# PCB_GW_ESP32_DIO_RS485.net
KiCad netlist of a schematic drawn in EAGLE
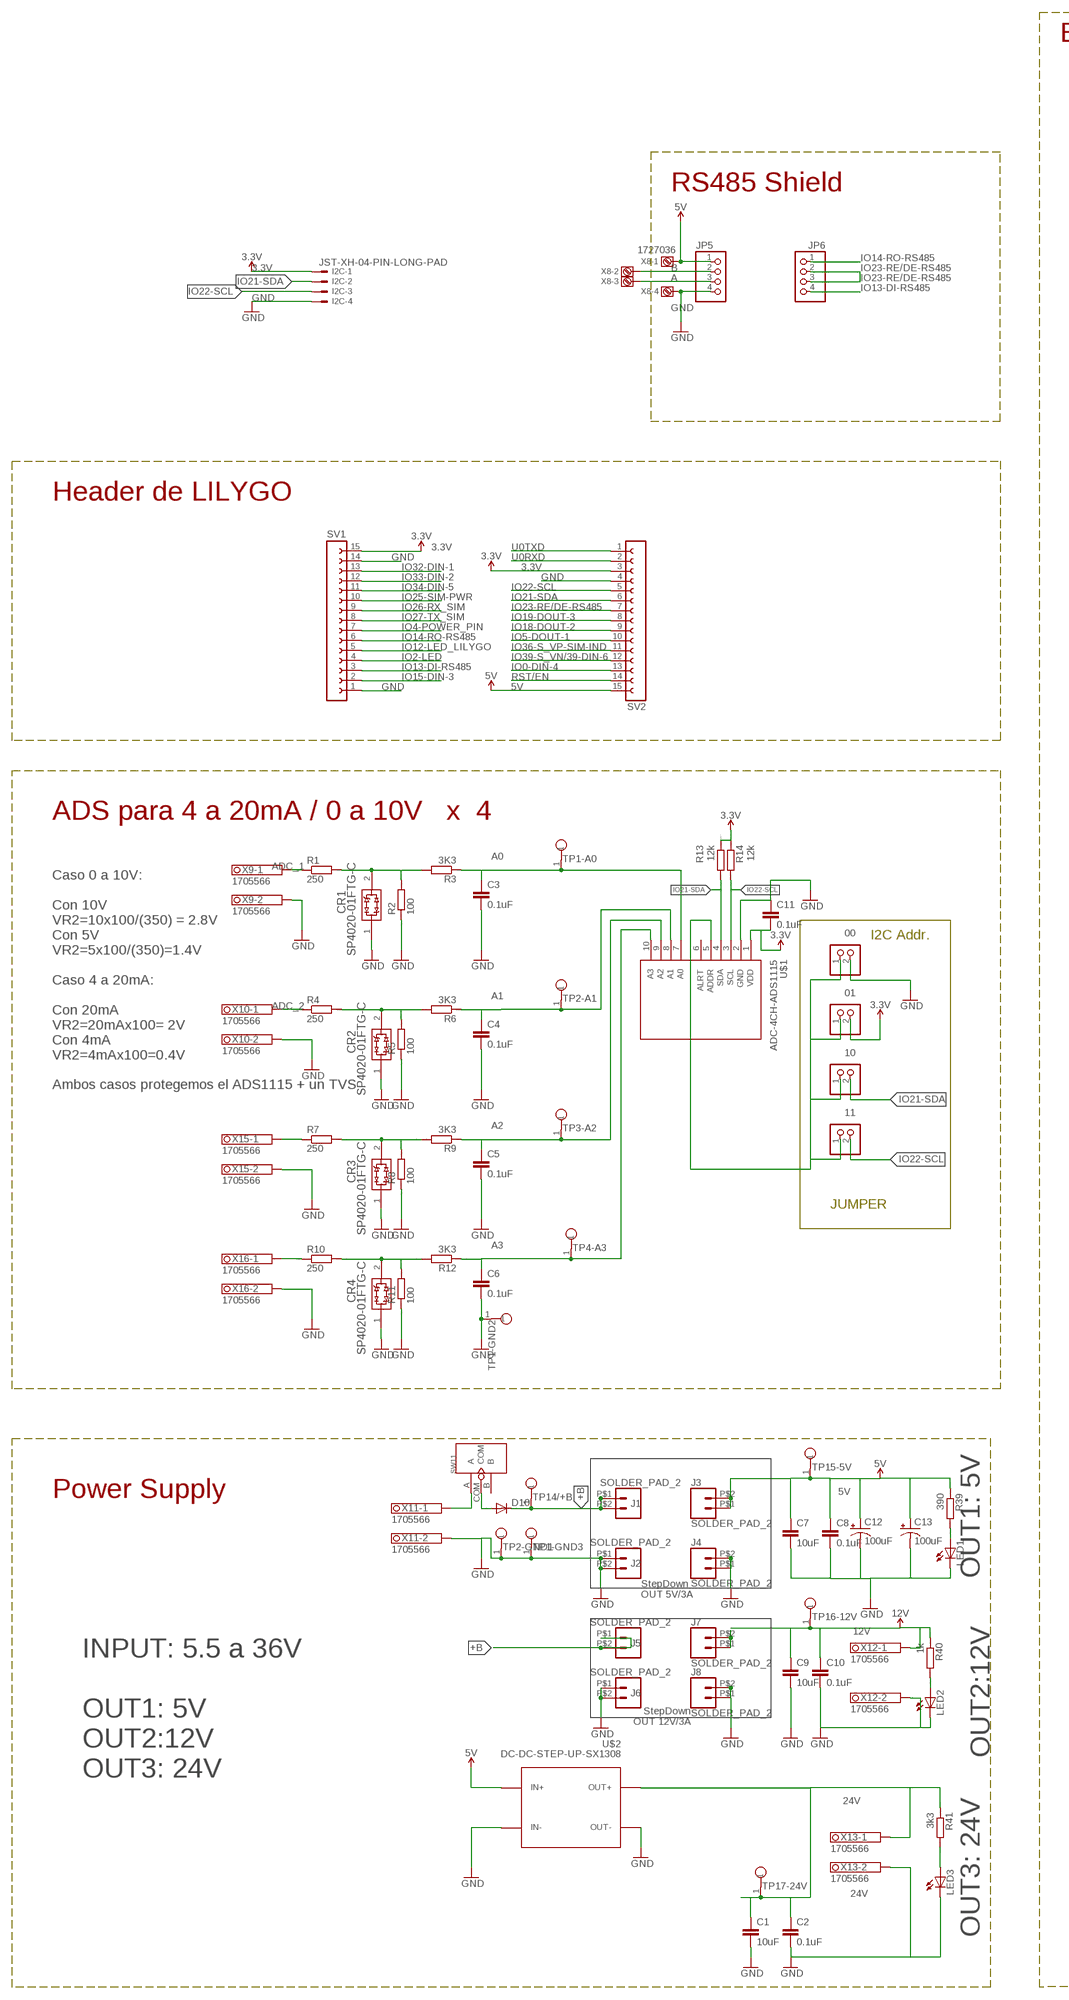
[diagram p0: schematic, sheet 1, part 1 of 2]
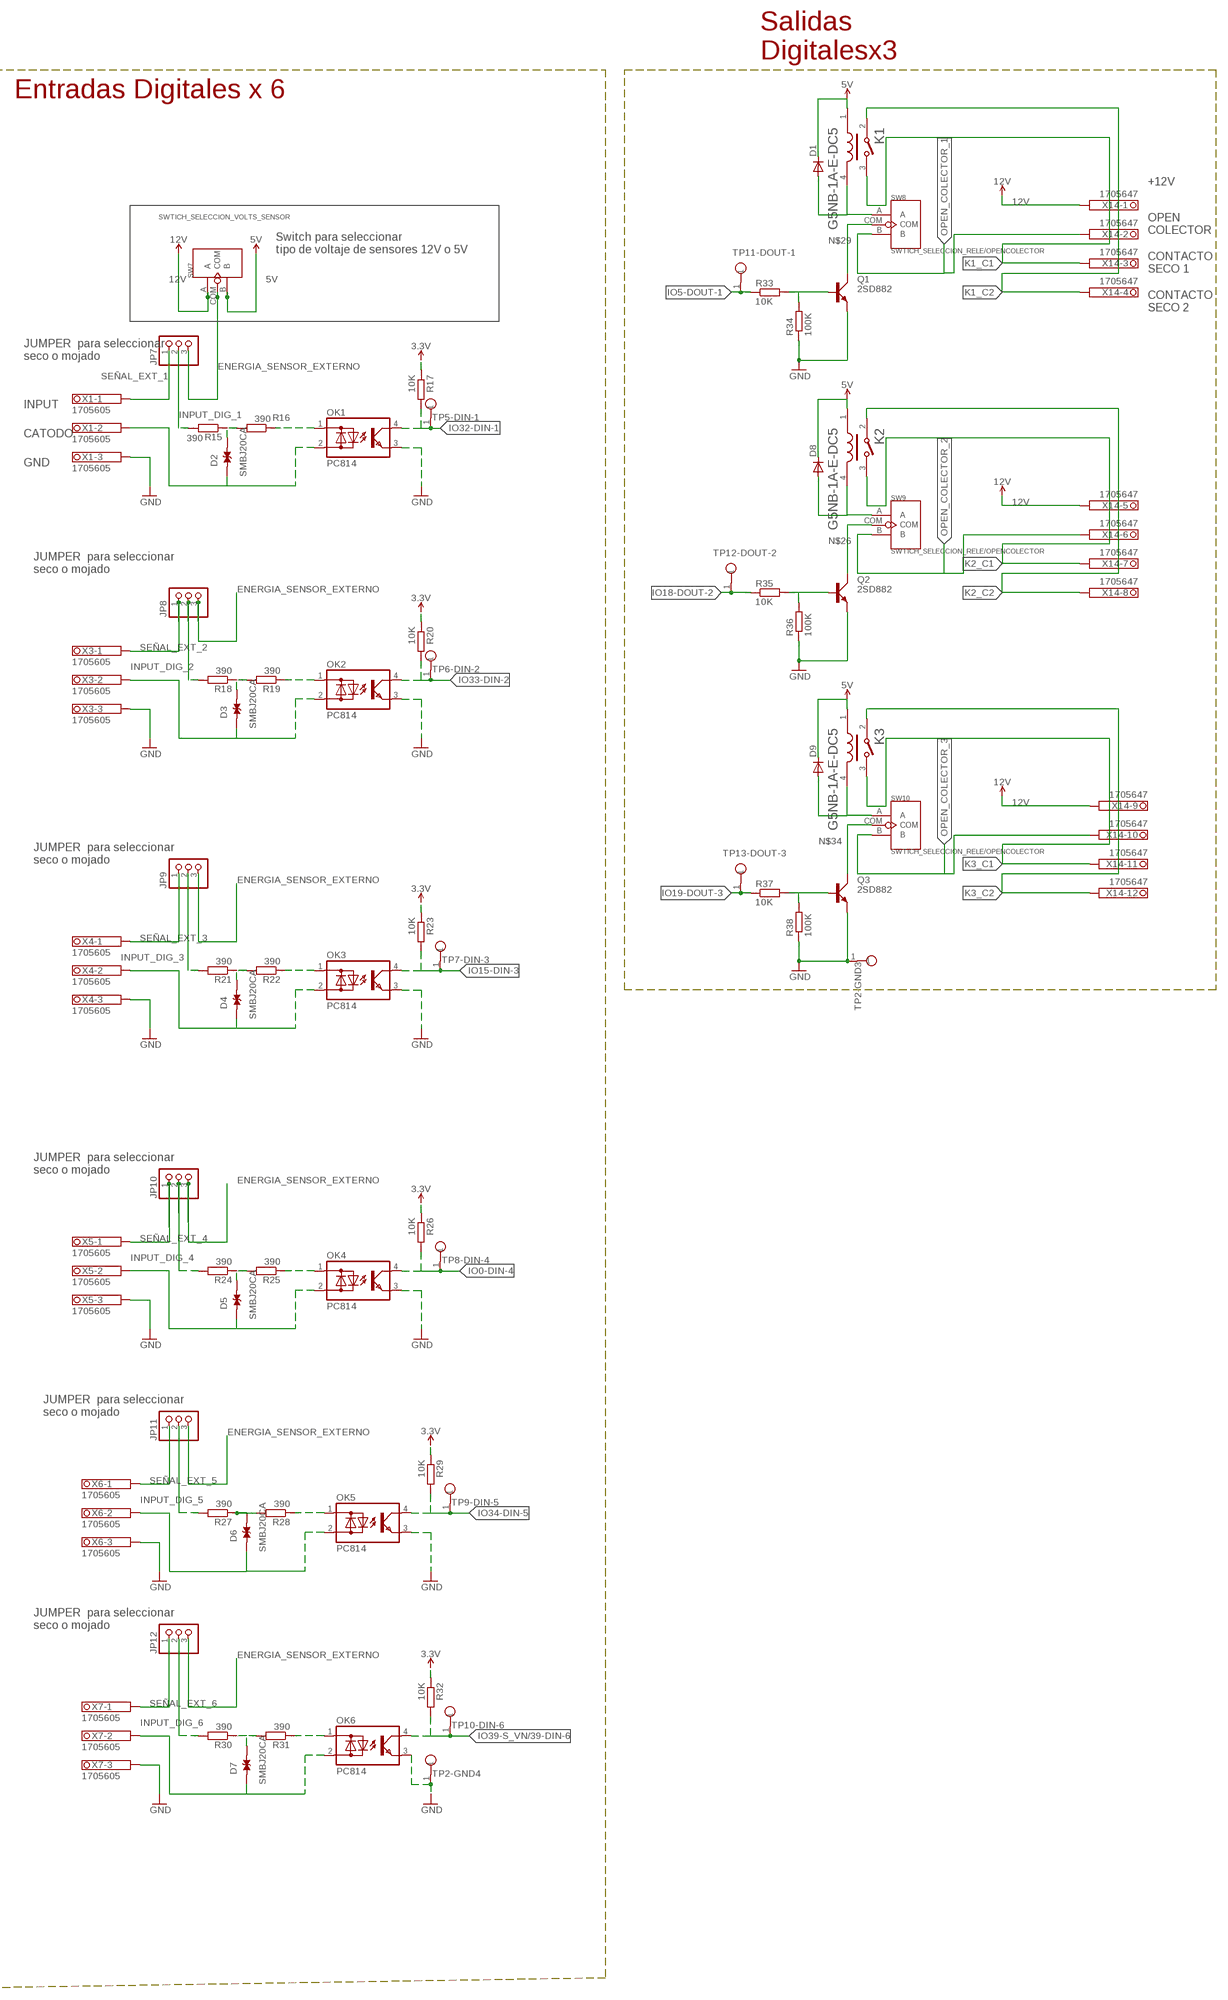
[diagram p1: schematic, sheet 1, part 2 of 2]

(export (version "E")
  (design (tool "Eeschema 10.0.6"))
  (components
    (comp (ref "C1")
      (value "10uF")
      (footprint "eagle-import:1206")
      (libsource (lib "eagle-import") (part "10UF-1206-6.3V-20%"))
    )
    (comp (ref "C2")
      (value "0.1uF")
      (footprint "eagle-import:1206")
      (libsource (lib "eagle-import") (part "1.0UF-1206-50V-10%"))
    )
    (comp (ref "C3")
      (value "0.1uF")
      (footprint "eagle-import:1206")
      (libsource (lib "eagle-import") (part "1.0UF-1206-50V-10%"))
    )
    (comp (ref "C4")
      (value "0.1uF")
      (footprint "eagle-import:1206")
      (libsource (lib "eagle-import") (part "1.0UF-1206-50V-10%"))
    )
    (comp (ref "C5")
      (value "0.1uF")
      (footprint "eagle-import:1206")
      (libsource (lib "eagle-import") (part "1.0UF-1206-50V-10%"))
    )
    (comp (ref "C6")
      (value "0.1uF")
      (footprint "eagle-import:1206")
      (libsource (lib "eagle-import") (part "1.0UF-1206-50V-10%"))
    )
    (comp (ref "C7")
      (value "10uF")
      (footprint "eagle-import:1206")
      (libsource (lib "eagle-import") (part "10UF-1206-6.3V-20%"))
    )
    (comp (ref "C8")
      (value "0.1uF")
      (footprint "eagle-import:1206")
      (libsource (lib "eagle-import") (part "1.0UF-1206-50V-10%"))
    )
    (comp (ref "C9")
      (value "10uF")
      (footprint "eagle-import:1206")
      (libsource (lib "eagle-import") (part "10UF-1206-6.3V-20%"))
    )
    (comp (ref "C10")
      (value "0.1uF")
      (footprint "eagle-import:1206")
      (libsource (lib "eagle-import") (part "1.0UF-1206-50V-10%"))
    )
    (comp (ref "C11")
      (value "0.1uF")
      (footprint "eagle-import:1206")
      (libsource (lib "eagle-import") (part "1.0UF-1206-50V-10%"))
    )
    (comp (ref "C12")
      (value "100uF")
      (footprint "eagle-import:CPOL-RADIAL-2.5MM-6.5MM")
      (libsource (lib "eagle-import") (part "100UF-POLAR-RADIAL-2.5MM-25V-20%"))
    )
    (comp (ref "C13")
      (value "100uF")
      (footprint "eagle-import:PANASONIC_D")
      (libsource (lib "eagle-import") (part "100UF-POLAR-25V-20%-SMD(ELEC)"))
    )
    (comp (ref "CR1")
      (value "SP4020-01FTG-C")
      (footprint "eagle-import:SOD323_LTF")
      (fields (field (name "COPYRIGHT") "Copyright (C) 2023 Ultra Librarian. All rights reserved."))
      (libsource (lib "eagle-import") (part "SP4020-01FTG-C"))
    )
    (comp (ref "CR2")
      (value "SP4020-01FTG-C")
      (footprint "eagle-import:SOD323_LTF")
      (fields (field (name "COPYRIGHT") "Copyright (C) 2023 Ultra Librarian. All rights reserved."))
      (libsource (lib "eagle-import") (part "SP4020-01FTG-C"))
    )
    (comp (ref "CR3")
      (value "SP4020-01FTG-C")
      (footprint "eagle-import:SOD323_LTF")
      (fields (field (name "COPYRIGHT") "Copyright (C) 2023 Ultra Librarian. All rights reserved."))
      (libsource (lib "eagle-import") (part "SP4020-01FTG-C"))
    )
    (comp (ref "CR4")
      (value "SP4020-01FTG-C")
      (footprint "eagle-import:SOD323_LTF")
      (fields (field (name "COPYRIGHT") "Copyright (C) 2023 Ultra Librarian. All rights reserved."))
      (libsource (lib "eagle-import") (part "SP4020-01FTG-C"))
    )
    (comp (ref "D1")
      (value "DIODE-DO214AC")
      (footprint "eagle-import:DO214AC")
      (libsource (lib "eagle-import") (part "DIODE-DO214AC"))
    )
    (comp (ref "D2")
      (value "SMBJ20CA")
      (footprint "eagle-import:DIOM4336X265N")
      (fields (field (name "MF") "Taiwan Semiconductor"))
      (libsource (lib "eagle-import") (part "SMBJ20CA"))
    )
    (comp (ref "D3")
      (value "SMBJ20CA")
      (footprint "eagle-import:DIOM4336X265N")
      (fields (field (name "MF") "Taiwan Semiconductor"))
      (libsource (lib "eagle-import") (part "SMBJ20CA"))
    )
    (comp (ref "D4")
      (value "SMBJ20CA")
      (footprint "eagle-import:DIOM4336X265N")
      (fields (field (name "MF") "Taiwan Semiconductor"))
      (libsource (lib "eagle-import") (part "SMBJ20CA"))
    )
    (comp (ref "D5")
      (value "SMBJ20CA")
      (footprint "eagle-import:DIOM4336X265N")
      (fields (field (name "MF") "Taiwan Semiconductor"))
      (libsource (lib "eagle-import") (part "SMBJ20CA"))
    )
    (comp (ref "D6")
      (value "SMBJ20CA")
      (footprint "eagle-import:DIOM4336X265N")
      (fields (field (name "MF") "Taiwan Semiconductor"))
      (libsource (lib "eagle-import") (part "SMBJ20CA"))
    )
    (comp (ref "D7")
      (value "SMBJ20CA")
      (footprint "eagle-import:DIOM4336X265N")
      (fields (field (name "MF") "Taiwan Semiconductor"))
      (libsource (lib "eagle-import") (part "SMBJ20CA"))
    )
    (comp (ref "D8")
      (value "DIODE-DO214AC")
      (footprint "eagle-import:DO214AC")
      (libsource (lib "eagle-import") (part "DIODE-DO214AC"))
    )
    (comp (ref "D9")
      (value "DIODE-DO214AC")
      (footprint "eagle-import:DO214AC")
      (libsource (lib "eagle-import") (part "DIODE-DO214AC"))
    )
    (comp (ref "D10")
      (value "DIODE-DO214AC")
      (footprint "eagle-import:DO214AC")
      (libsource (lib "eagle-import") (part "DIODE-DO214AC"))
    )
    (comp (ref "I2C")
      (value "JST-XH-04-PIN-LONG-PAD")
      (footprint "eagle-import:JST-XH-04-PACKAGE-LONG-PAD")
      (libsource (lib "eagle-import") (part "JST-XH-04-PIN-LONG-PAD"))
    )
    (comp (ref "J1")
      (value "SOLDER_PAD_2")
      (footprint "eagle-import:SOLDER_PAD_2")
      (libsource (lib "eagle-import") (part "SOLDER_PAD_2"))
    )
    (comp (ref "J2")
      (value "SOLDER_PAD_2")
      (footprint "eagle-import:SOLDER_PAD_2")
      (libsource (lib "eagle-import") (part "SOLDER_PAD_2"))
    )
    (comp (ref "J3")
      (value "SOLDER_PAD_2")
      (footprint "eagle-import:SOLDER_PAD_2")
      (libsource (lib "eagle-import") (part "SOLDER_PAD_2"))
    )
    (comp (ref "J4")
      (value "SOLDER_PAD_2")
      (footprint "eagle-import:SOLDER_PAD_2")
      (libsource (lib "eagle-import") (part "SOLDER_PAD_2"))
    )
    (comp (ref "J5")
      (value "SOLDER_PAD_2")
      (footprint "eagle-import:SOLDER_PAD_2")
      (libsource (lib "eagle-import") (part "SOLDER_PAD_2"))
    )
    (comp (ref "J6")
      (value "SOLDER_PAD_2")
      (footprint "eagle-import:SOLDER_PAD_2")
      (libsource (lib "eagle-import") (part "SOLDER_PAD_2"))
    )
    (comp (ref "J7")
      (value "SOLDER_PAD_2")
      (footprint "eagle-import:SOLDER_PAD_2")
      (libsource (lib "eagle-import") (part "SOLDER_PAD_2"))
    )
    (comp (ref "J8")
      (value "SOLDER_PAD_2")
      (footprint "eagle-import:SOLDER_PAD_2")
      (libsource (lib "eagle-import") (part "SOLDER_PAD_2"))
    )
    (comp (ref "JP1")
      (value "00")
      (footprint "eagle-import:1X02")
      (libsource (lib "eagle-import") (part "PINHD-1X2"))
    )
    (comp (ref "JP2")
      (value "01")
      (footprint "eagle-import:1X02")
      (libsource (lib "eagle-import") (part "PINHD-1X2"))
    )
    (comp (ref "JP3")
      (value "10")
      (footprint "eagle-import:1X02")
      (libsource (lib "eagle-import") (part "PINHD-1X2"))
    )
    (comp (ref "JP4")
      (value "11")
      (footprint "eagle-import:1X02")
      (libsource (lib "eagle-import") (part "PINHD-1X2"))
    )
    (comp (ref "JP5")
      (value "PINHD-1X4")
      (footprint "eagle-import:1X04")
      (libsource (lib "eagle-import") (part "PINHD-1X4"))
    )
    (comp (ref "JP6")
      (value "PINHD-1X4")
      (footprint "eagle-import:1X04")
      (libsource (lib "eagle-import") (part "PINHD-1X4"))
    )
    (comp (ref "JP7")
      (value "PINHD-1X3")
      (footprint "eagle-import:1X03")
      (libsource (lib "eagle-import") (part "PINHD-1X3"))
    )
    (comp (ref "JP8")
      (value "PINHD-1X3")
      (footprint "eagle-import:1X03")
      (libsource (lib "eagle-import") (part "PINHD-1X3"))
    )
    (comp (ref "JP9")
      (value "PINHD-1X3")
      (footprint "eagle-import:1X03")
      (libsource (lib "eagle-import") (part "PINHD-1X3"))
    )
    (comp (ref "JP10")
      (value "PINHD-1X3")
      (footprint "eagle-import:1X03")
      (libsource (lib "eagle-import") (part "PINHD-1X3"))
    )
    (comp (ref "JP11")
      (value "PINHD-1X3")
      (footprint "eagle-import:1X03")
      (libsource (lib "eagle-import") (part "PINHD-1X3"))
    )
    (comp (ref "JP12")
      (value "PINHD-1X3")
      (footprint "eagle-import:1X03")
      (libsource (lib "eagle-import") (part "PINHD-1X3"))
    )
    (comp (ref "K1")
      (value "OMRON_G5NB-1A-E-DC5OMRON_G5NB-1A-E-DC5_0_0")
      (footprint "eagle-import:OMRON_G5NB-1A-E-DC5_0")
      (fields
        (field (name "DIGIKEY_PART_NUMBER") "Z2771-ND")
        (field (name "MF") "Omron")
        (field (name "MOUSER_PART_NUMBER") "653-G5NB-1A-E-DC5")
      )
      (libsource (lib "eagle-import") (part "OMRON_G5NB-1A-E-DC5OMRON_G5NB-1A-E-DC5_0_0"))
    )
    (comp (ref "K2")
      (value "OMRON_G5NB-1A-E-DC5OMRON_G5NB-1A-E-DC5_0_0")
      (footprint "eagle-import:OMRON_G5NB-1A-E-DC5_0")
      (fields
        (field (name "DIGIKEY_PART_NUMBER") "Z2771-ND")
        (field (name "MF") "Omron")
        (field (name "MOUSER_PART_NUMBER") "653-G5NB-1A-E-DC5")
      )
      (libsource (lib "eagle-import") (part "OMRON_G5NB-1A-E-DC5OMRON_G5NB-1A-E-DC5_0_0"))
    )
    (comp (ref "K3")
      (value "OMRON_G5NB-1A-E-DC5OMRON_G5NB-1A-E-DC5_0_0")
      (footprint "eagle-import:OMRON_G5NB-1A-E-DC5_0")
      (fields
        (field (name "DIGIKEY_PART_NUMBER") "Z2771-ND")
        (field (name "MF") "Omron")
        (field (name "MOUSER_PART_NUMBER") "653-G5NB-1A-E-DC5")
      )
      (libsource (lib "eagle-import") (part "OMRON_G5NB-1A-E-DC5OMRON_G5NB-1A-E-DC5_0_0"))
    )
    (comp (ref "LED1")
      (value "LEDCHIPLED_1206")
      (footprint "eagle-import:CHIPLED_1206")
      (libsource (lib "eagle-import") (part "LEDCHIPLED_1206"))
    )
    (comp (ref "LED2")
      (value "LEDCHIPLED_1206")
      (footprint "eagle-import:CHIPLED_1206")
      (libsource (lib "eagle-import") (part "LEDCHIPLED_1206"))
    )
    (comp (ref "LED3")
      (value "LEDCHIPLED_1206")
      (footprint "eagle-import:CHIPLED_1206")
      (libsource (lib "eagle-import") (part "LEDCHIPLED_1206"))
    )
    (comp (ref "OK1")
      (value "PC814")
      (footprint "eagle-import:DIL04")
      (libsource (lib "eagle-import") (part "PC814"))
    )
    (comp (ref "OK2")
      (value "PC814")
      (footprint "eagle-import:DIL04")
      (libsource (lib "eagle-import") (part "PC814"))
    )
    (comp (ref "OK3")
      (value "PC814")
      (footprint "eagle-import:DIL04")
      (libsource (lib "eagle-import") (part "PC814"))
    )
    (comp (ref "OK4")
      (value "PC814")
      (footprint "eagle-import:DIL04")
      (libsource (lib "eagle-import") (part "PC814"))
    )
    (comp (ref "OK5")
      (value "PC814")
      (footprint "eagle-import:DIL04")
      (libsource (lib "eagle-import") (part "PC814"))
    )
    (comp (ref "OK6")
      (value "PC814")
      (footprint "eagle-import:DIL04")
      (libsource (lib "eagle-import") (part "PC814"))
    )
    (comp (ref "Q1")
      (value "2SD882")
      (footprint "eagle-import:TO126AV")
      (libsource (lib "eagle-import") (part "BD437"))
    )
    (comp (ref "Q2")
      (value "2SD882")
      (footprint "eagle-import:TO126AV")
      (libsource (lib "eagle-import") (part "BD437"))
    )
    (comp (ref "Q3")
      (value "2SD882")
      (footprint "eagle-import:TO126AV")
      (libsource (lib "eagle-import") (part "BD437"))
    )
    (comp (ref "R1")
      (value "250")
      (footprint "eagle-import:R1206")
      (libsource (lib "eagle-import") (part "RR1206"))
    )
    (comp (ref "R2")
      (value "100")
      (footprint "eagle-import:R1206")
      (libsource (lib "eagle-import") (part "RR1206"))
    )
    (comp (ref "R3")
      (value "3K3")
      (footprint "eagle-import:R1206")
      (libsource (lib "eagle-import") (part "RR1206"))
    )
    (comp (ref "R4")
      (value "250")
      (footprint "eagle-import:R1206")
      (libsource (lib "eagle-import") (part "RR1206"))
    )
    (comp (ref "R5")
      (value "100")
      (footprint "eagle-import:R1206")
      (libsource (lib "eagle-import") (part "RR1206"))
    )
    (comp (ref "R6")
      (value "3K3")
      (footprint "eagle-import:R1206")
      (libsource (lib "eagle-import") (part "RR1206"))
    )
    (comp (ref "R7")
      (value "250")
      (footprint "eagle-import:R1206")
      (libsource (lib "eagle-import") (part "RR1206"))
    )
    (comp (ref "R8")
      (value "100")
      (footprint "eagle-import:R1206")
      (libsource (lib "eagle-import") (part "RR1206"))
    )
    (comp (ref "R9")
      (value "3K3")
      (footprint "eagle-import:R1206")
      (libsource (lib "eagle-import") (part "RR1206"))
    )
    (comp (ref "R10")
      (value "250")
      (footprint "eagle-import:R1206")
      (libsource (lib "eagle-import") (part "RR1206"))
    )
    (comp (ref "R11")
      (value "100")
      (footprint "eagle-import:R1206")
      (libsource (lib "eagle-import") (part "RR1206"))
    )
    (comp (ref "R12")
      (value "3K3")
      (footprint "eagle-import:R1206")
      (libsource (lib "eagle-import") (part "RR1206"))
    )
    (comp (ref "R13")
      (value "12k")
      (footprint "eagle-import:R1206")
      (libsource (lib "eagle-import") (part "RR1206"))
    )
    (comp (ref "R14")
      (value "12k")
      (footprint "eagle-import:R1206")
      (libsource (lib "eagle-import") (part "RR1206"))
    )
    (comp (ref "R15")
      (value "390")
      (footprint "eagle-import:R1206")
      (libsource (lib "eagle-import") (part "RR1206"))
    )
    (comp (ref "R16")
      (value "390")
      (footprint "eagle-import:R1206")
      (libsource (lib "eagle-import") (part "RR1206"))
    )
    (comp (ref "R17")
      (value "10K")
      (footprint "eagle-import:R1206")
      (libsource (lib "eagle-import") (part "RR1206"))
    )
    (comp (ref "R18")
      (value "390")
      (footprint "eagle-import:R1206")
      (libsource (lib "eagle-import") (part "RR1206"))
    )
    (comp (ref "R19")
      (value "390")
      (footprint "eagle-import:R1206")
      (libsource (lib "eagle-import") (part "RR1206"))
    )
    (comp (ref "R20")
      (value "10K")
      (footprint "eagle-import:R1206")
      (libsource (lib "eagle-import") (part "RR1206"))
    )
    (comp (ref "R21")
      (value "390")
      (footprint "eagle-import:R1206")
      (libsource (lib "eagle-import") (part "RR1206"))
    )
    (comp (ref "R22")
      (value "390")
      (footprint "eagle-import:R1206")
      (libsource (lib "eagle-import") (part "RR1206"))
    )
    (comp (ref "R23")
      (value "10K")
      (footprint "eagle-import:R1206")
      (libsource (lib "eagle-import") (part "RR1206"))
    )
    (comp (ref "R24")
      (value "390")
      (footprint "eagle-import:R1206")
      (libsource (lib "eagle-import") (part "RR1206"))
    )
    (comp (ref "R25")
      (value "390")
      (footprint "eagle-import:R1206")
      (libsource (lib "eagle-import") (part "RR1206"))
    )
    (comp (ref "R26")
      (value "10K")
      (footprint "eagle-import:R1206")
      (libsource (lib "eagle-import") (part "RR1206"))
    )
    (comp (ref "R27")
      (value "390")
      (footprint "eagle-import:R1206")
      (libsource (lib "eagle-import") (part "RR1206"))
    )
    (comp (ref "R28")
      (value "390")
      (footprint "eagle-import:R1206")
      (libsource (lib "eagle-import") (part "RR1206"))
    )
    (comp (ref "R29")
      (value "10K")
      (footprint "eagle-import:R1206")
      (libsource (lib "eagle-import") (part "RR1206"))
    )
    (comp (ref "R30")
      (value "390")
      (footprint "eagle-import:R1206")
      (libsource (lib "eagle-import") (part "RR1206"))
    )
    (comp (ref "R31")
      (value "390")
      (footprint "eagle-import:R1206")
      (libsource (lib "eagle-import") (part "RR1206"))
    )
    (comp (ref "R32")
      (value "10K")
      (footprint "eagle-import:R1206")
      (libsource (lib "eagle-import") (part "RR1206"))
    )
    (comp (ref "R33")
      (value "10K")
      (footprint "eagle-import:R1206")
      (libsource (lib "eagle-import") (part "RR1206"))
    )
    (comp (ref "R34")
      (value "100K")
      (footprint "eagle-import:R1206")
      (libsource (lib "eagle-import") (part "RR1206"))
    )
    (comp (ref "R35")
      (value "10K")
      (footprint "eagle-import:R1206")
      (libsource (lib "eagle-import") (part "RR1206"))
    )
    (comp (ref "R36")
      (value "100K")
      (footprint "eagle-import:R1206")
      (libsource (lib "eagle-import") (part "RR1206"))
    )
    (comp (ref "R37")
      (value "10K")
      (footprint "eagle-import:R1206")
      (libsource (lib "eagle-import") (part "RR1206"))
    )
    (comp (ref "R38")
      (value "100K")
      (footprint "eagle-import:R1206")
      (libsource (lib "eagle-import") (part "RR1206"))
    )
    (comp (ref "R39")
      (value "390")
      (footprint "eagle-import:R1206")
      (libsource (lib "eagle-import") (part "RR1206"))
    )
    (comp (ref "R40")
      (value "1k")
      (footprint "eagle-import:R1206")
      (libsource (lib "eagle-import") (part "RR1206"))
    )
    (comp (ref "R41")
      (value "3k3")
      (footprint "eagle-import:R1206")
      (libsource (lib "eagle-import") (part "RR1206"))
    )
    (comp (ref "SV1")
      (value "FE15-1")
      (footprint "eagle-import:FE15")
      (libsource (lib "eagle-import") (part "FE15-1"))
    )
    (comp (ref "SV2")
      (value "FE15-1")
      (footprint "eagle-import:FE15")
      (libsource (lib "eagle-import") (part "FE15-1"))
    )
    (comp (ref "SW7")
      (value "SWTICH_SELECCION_VOLTS_SENSOR")
      (footprint "eagle-import:SW5-2.0-8.8X4.4X4.7MM-90D")
      (fields (field (name "MPN") "3P-2.0-90D3P-2.0-90D-REINFORCE"))
      (libsource (lib "eagle-import") (part "DIP-TOGGLE-SWITCH-ON-ON(3+2P-8.8X4.6MM)-90D"))
    )
    (comp (ref "SW8")
      (value "SWTICH_SELECCION_RELE/OPENCOLECTOR")
      (footprint "eagle-import:SW5-2.0-8.8X4.4X4.7MM-90D")
      (fields (field (name "MPN") "3P-2.0-90D3P-2.0-90D-REINFORCE"))
      (libsource (lib "eagle-import") (part "DIP-TOGGLE-SWITCH-ON-ON(3+2P-8.8X4.6MM)-90D"))
    )
    (comp (ref "SW9")
      (value "SWTICH_SELECCION_RELE/OPENCOLECTOR")
      (footprint "eagle-import:SW5-2.0-8.8X4.4X4.7MM-90D")
      (fields (field (name "MPN") "3P-2.0-90D3P-2.0-90D-REINFORCE"))
      (libsource (lib "eagle-import") (part "DIP-TOGGLE-SWITCH-ON-ON(3+2P-8.8X4.6MM)-90D"))
    )
    (comp (ref "SW10")
      (value "SWTICH_SELECCION_RELE/OPENCOLECTOR")
      (footprint "eagle-import:SW5-2.0-8.8X4.4X4.7MM-90D")
      (fields (field (name "MPN") "3P-2.0-90D3P-2.0-90D-REINFORCE"))
      (libsource (lib "eagle-import") (part "DIP-TOGGLE-SWITCH-ON-ON(3+2P-8.8X4.6MM)-90D"))
    )
    (comp (ref "SW11")
      (value "DIP-TOGGLE-SWITCH-ON-ON(3+2P-8.8X4.6MM)-90D")
      (footprint "eagle-import:SW5-2.0-8.8X4.4X4.7MM-90D")
      (fields (field (name "MPN") "3P-2.0-90D3P-2.0-90D-REINFORCE"))
      (libsource (lib "eagle-import") (part "DIP-TOGGLE-SWITCH-ON-ON(3+2P-8.8X4.6MM)-90D"))
    )
    (comp (ref "TP1-A0")
      (value "TESTPOINT")
      (footprint "eagle-import:TESTPOINT")
      (libsource (lib "eagle-import") (part "TESTPOINT"))
    )
    (comp (ref "TP1-GND2")
      (value "TESTPOINT")
      (footprint "eagle-import:TESTPOINT")
      (libsource (lib "eagle-import") (part "TESTPOINT"))
    )
    (comp (ref "TP1-GND3")
      (value "TESTPOINT")
      (footprint "eagle-import:TESTPOINT")
      (libsource (lib "eagle-import") (part "TESTPOINT"))
    )
    (comp (ref "TP2-A1")
      (value "TESTPOINT")
      (footprint "eagle-import:TESTPOINT")
      (libsource (lib "eagle-import") (part "TESTPOINT"))
    )
    (comp (ref "TP2-GND1")
      (value "TESTPOINT")
      (footprint "eagle-import:TESTPOINT")
      (libsource (lib "eagle-import") (part "TESTPOINT"))
    )
    (comp (ref "TP2-GND3")
      (value "TESTPOINT")
      (footprint "eagle-import:TESTPOINT")
      (libsource (lib "eagle-import") (part "TESTPOINT"))
    )
    (comp (ref "TP2-GND4")
      (value "TESTPOINT")
      (footprint "eagle-import:TESTPOINT")
      (libsource (lib "eagle-import") (part "TESTPOINT"))
    )
    (comp (ref "TP3-A2")
      (value "TESTPOINT")
      (footprint "eagle-import:TESTPOINT")
      (libsource (lib "eagle-import") (part "TESTPOINT"))
    )
    (comp (ref "TP4-A3")
      (value "TESTPOINT")
      (footprint "eagle-import:TESTPOINT")
      (libsource (lib "eagle-import") (part "TESTPOINT"))
    )
    (comp (ref "TP5-DIN-1")
      (value "TESTPOINT")
      (footprint "eagle-import:TESTPOINT")
      (libsource (lib "eagle-import") (part "TESTPOINT"))
    )
    (comp (ref "TP6-DIN-2")
      (value "TESTPOINT")
      (footprint "eagle-import:TESTPOINT")
      (libsource (lib "eagle-import") (part "TESTPOINT"))
    )
    (comp (ref "TP7-DIN-3")
      (value "TESTPOINT")
      (footprint "eagle-import:TESTPOINT")
      (libsource (lib "eagle-import") (part "TESTPOINT"))
    )
    (comp (ref "TP8-DIN-4")
      (value "TESTPOINT")
      (footprint "eagle-import:TESTPOINT")
      (libsource (lib "eagle-import") (part "TESTPOINT"))
    )
    (comp (ref "TP9-DIN-5")
      (value "TESTPOINT")
      (footprint "eagle-import:TESTPOINT")
      (libsource (lib "eagle-import") (part "TESTPOINT"))
    )
    (comp (ref "TP10-DIN-6")
      (value "TESTPOINT")
      (footprint "eagle-import:TESTPOINT")
      (libsource (lib "eagle-import") (part "TESTPOINT"))
    )
    (comp (ref "TP11-DOUT-1")
      (value "TESTPOINT")
      (footprint "eagle-import:TESTPOINT")
      (libsource (lib "eagle-import") (part "TESTPOINT"))
    )
    (comp (ref "TP12-DOUT-2")
      (value "TESTPOINT")
      (footprint "eagle-import:TESTPOINT")
      (libsource (lib "eagle-import") (part "TESTPOINT"))
    )
    (comp (ref "TP13-DOUT-3")
      (value "TESTPOINT")
      (footprint "eagle-import:TESTPOINT")
      (libsource (lib "eagle-import") (part "TESTPOINT"))
    )
    (comp (ref "TP14/+B")
      (value "TESTPOINT")
      (footprint "eagle-import:TESTPOINT")
      (libsource (lib "eagle-import") (part "TESTPOINT"))
    )
    (comp (ref "TP15-5V")
      (value "TESTPOINT")
      (footprint "eagle-import:TESTPOINT")
      (libsource (lib "eagle-import") (part "TESTPOINT"))
    )
    (comp (ref "TP16-12V")
      (value "TESTPOINT")
      (footprint "eagle-import:TESTPOINT")
      (libsource (lib "eagle-import") (part "TESTPOINT"))
    )
    (comp (ref "TP17-24V")
      (value "TESTPOINT")
      (footprint "eagle-import:TESTPOINT")
      (libsource (lib "eagle-import") (part "TESTPOINT"))
    )
    (comp (ref "U$1")
      (value "ADC-4CH-ADS1115")
      (footprint "eagle-import:ADC-4CH-ADS1115")
      (libsource (lib "eagle-import") (part "ADC-4CH-ADS1115"))
    )
    (comp (ref "U$2")
      (value "DC-DC-STEP-UP-SX1308")
      (footprint "eagle-import:DC-DC-STEP-UP-SX1308")
      (libsource (lib "eagle-import") (part "DC-DC-STEP-UP-SX1308"))
    )
    (comp (ref "X1")
      (value "1705605")
      (footprint "eagle-import:1705605")
      (libsource (lib "eagle-import") (part "1705605"))
    )
    (comp (ref "X3")
      (value "1705605")
      (footprint "eagle-import:1705605")
      (libsource (lib "eagle-import") (part "1705605"))
    )
    (comp (ref "X4")
      (value "1705605")
      (footprint "eagle-import:1705605")
      (libsource (lib "eagle-import") (part "1705605"))
    )
    (comp (ref "X5")
      (value "1705605")
      (footprint "eagle-import:1705605")
      (libsource (lib "eagle-import") (part "1705605"))
    )
    (comp (ref "X6")
      (value "1705605")
      (footprint "eagle-import:1705605")
      (libsource (lib "eagle-import") (part "1705605"))
    )
    (comp (ref "X7")
      (value "1705605")
      (footprint "eagle-import:1705605")
      (libsource (lib "eagle-import") (part "1705605"))
    )
    (comp (ref "X8")
      (value "1727036")
      (footprint "eagle-import:1727036")
      (fields (field (name "MF") "FARNELL"))
      (libsource (lib "eagle-import") (part "1727036"))
    )
    (comp (ref "X9")
      (value "1705566")
      (footprint "eagle-import:1705566")
      (libsource (lib "eagle-import") (part "1705566"))
    )
    (comp (ref "X10")
      (value "1705566")
      (footprint "eagle-import:1705566")
      (libsource (lib "eagle-import") (part "1705566"))
    )
    (comp (ref "X11")
      (value "1705566")
      (footprint "eagle-import:1705566")
      (libsource (lib "eagle-import") (part "1705566"))
    )
    (comp (ref "X12")
      (value "1705566")
      (footprint "eagle-import:1705566")
      (libsource (lib "eagle-import") (part "1705566"))
    )
    (comp (ref "X13")
      (value "1705566")
      (footprint "eagle-import:1705566")
      (libsource (lib "eagle-import") (part "1705566"))
    )
    (comp (ref "X14")
      (value "1705647")
      (footprint "eagle-import:1705647")
      (libsource (lib "eagle-import") (part "1705647"))
    )
    (comp (ref "X15")
      (value "1705566")
      (footprint "eagle-import:1705566")
      (libsource (lib "eagle-import") (part "1705566"))
    )
    (comp (ref "X16")
      (value "1705566")
      (footprint "eagle-import:1705566")
      (libsource (lib "eagle-import") (part "1705566"))
    )
  )
  (nets
    (net (code "1") (name "+B") (class "Default")
      (node (ref "D10") (pin "C") (pinfunction "C_C") (pintype "passive"))
      (node (ref "J1") (pin "P$1") (pinfunction "1_P$1") (pintype "passive"))
      (node (ref "J1") (pin "P$2") (pinfunction "2_P$2") (pintype "passive"))
      (node (ref "J5") (pin "P$1") (pinfunction "1_P$1") (pintype "passive"))
      (node (ref "J5") (pin "P$2") (pinfunction "2_P$2") (pintype "passive"))
      (node (ref "TP14/+B") (pin "1") (pinfunction "1_1") (pintype "passive"))
    )
    (net (code "2") (name "/24V") (class "Default")
      (node (ref "C1") (pin "1") (pinfunction "1_1") (pintype "passive"))
      (node (ref "C2") (pin "1") (pinfunction "1_1") (pintype "passive"))
      (node (ref "R41") (pin "1") (pinfunction "1_1") (pintype "passive"))
      (node (ref "TP17-24V") (pin "1") (pinfunction "1_1") (pintype "passive"))
      (node (ref "U$2") (pin "OUT+") (pinfunction "OUT+_OUT+") (pintype "bidirectional"))
      (node (ref "X13") (pin "1.1") (pinfunction "1A_1.1") (pintype "passive"))
      (node (ref "X13") (pin "1.2") (pinfunction "1A_1.2") (pintype "passive"))
    )
    (net (code "3") (name "/A") (class "Default")
      (node (ref "JP5") (pin "3") (pinfunction "3_3") (pintype "passive"))
      (node (ref "X8") (pin "3") (pinfunction "1_3") (pintype "passive"))
    )
    (net (code "4") (name "/A0") (class "Default")
      (node (ref "C3") (pin "1") (pinfunction "1_1") (pintype "passive"))
      (node (ref "R3") (pin "1") (pinfunction "1_1") (pintype "passive"))
      (node (ref "TP1-A0") (pin "1") (pinfunction "1_1") (pintype "passive"))
      (node (ref "U$1") (pin "7") (pinfunction "A0_7") (pintype "input"))
    )
    (net (code "5") (name "/A1") (class "Default")
      (node (ref "C4") (pin "1") (pinfunction "1_1") (pintype "passive"))
      (node (ref "R6") (pin "1") (pinfunction "1_1") (pintype "passive"))
      (node (ref "TP2-A1") (pin "1") (pinfunction "1_1") (pintype "passive"))
      (node (ref "U$1") (pin "8") (pinfunction "A1_8") (pintype "input"))
    )
    (net (code "6") (name "/A2") (class "Default")
      (node (ref "C5") (pin "1") (pinfunction "1_1") (pintype "passive"))
      (node (ref "R9") (pin "1") (pinfunction "1_1") (pintype "passive"))
      (node (ref "TP3-A2") (pin "1") (pinfunction "1_1") (pintype "passive"))
      (node (ref "U$1") (pin "9") (pinfunction "A2_9") (pintype "input"))
    )
    (net (code "7") (name "/A3") (class "Default")
      (node (ref "C6") (pin "1") (pinfunction "1_1") (pintype "passive"))
      (node (ref "R12") (pin "1") (pinfunction "1_1") (pintype "passive"))
      (node (ref "TP4-A3") (pin "1") (pinfunction "1_1") (pintype "passive"))
      (node (ref "U$1") (pin "10") (pinfunction "A3_10") (pintype "input"))
    )
    (net (code "8") (name "/ADC_1") (class "Default")
      (node (ref "R1") (pin "1") (pinfunction "1_1") (pintype "passive"))
      (node (ref "X9") (pin "1.1") (pinfunction "1A_1.1") (pintype "passive"))
      (node (ref "X9") (pin "1.2") (pinfunction "1A_1.2") (pintype "passive"))
    )
    (net (code "9") (name "/ADC_2") (class "Default")
      (node (ref "R4") (pin "1") (pinfunction "1_1") (pintype "passive"))
      (node (ref "X10") (pin "1.1") (pinfunction "1A_1.1") (pintype "passive"))
      (node (ref "X10") (pin "1.2") (pinfunction "1A_1.2") (pintype "passive"))
    )
    (net (code "10") (name "/B") (class "Default")
      (node (ref "JP5") (pin "2") (pinfunction "2_2") (pintype "passive"))
      (node (ref "X8") (pin "2") (pinfunction "1_2") (pintype "passive"))
    )
    (net (code "11") (name "/ENERGIA_SENSOR_EXTERNO") (class "Default")
      (node (ref "JP10") (pin "3") (pinfunction "3_3") (pintype "passive"))
      (node (ref "JP11") (pin "3") (pinfunction "3_3") (pintype "passive"))
      (node (ref "JP12") (pin "3") (pinfunction "3_3") (pintype "passive"))
      (node (ref "JP7") (pin "3") (pinfunction "3_3") (pintype "passive"))
      (node (ref "JP8") (pin "3") (pinfunction "3_3") (pintype "passive"))
      (node (ref "JP9") (pin "3") (pinfunction "3_3") (pintype "passive"))
      (node (ref "SW7") (pin "COM") (pinfunction "COM_COM") (pintype "bidirectional"))
    )
    (net (code "12") (name "/INPUT_DIG_1") (class "Default")
      (node (ref "JP7") (pin "2") (pinfunction "2_2") (pintype "passive"))
      (node (ref "R15") (pin "2") (pinfunction "2_2") (pintype "passive"))
    )
    (net (code "13") (name "/INPUT_DIG_2") (class "Default")
      (node (ref "JP8") (pin "2") (pinfunction "2_2") (pintype "passive"))
      (node (ref "R18") (pin "2") (pinfunction "2_2") (pintype "passive"))
    )
    (net (code "14") (name "/INPUT_DIG_3") (class "Default")
      (node (ref "JP9") (pin "2") (pinfunction "2_2") (pintype "passive"))
      (node (ref "R21") (pin "2") (pinfunction "2_2") (pintype "passive"))
    )
    (net (code "15") (name "/INPUT_DIG_4") (class "Default")
      (node (ref "JP10") (pin "2") (pinfunction "2_2") (pintype "passive"))
      (node (ref "R24") (pin "2") (pinfunction "2_2") (pintype "passive"))
    )
    (net (code "16") (name "/INPUT_DIG_5") (class "Default")
      (node (ref "JP11") (pin "2") (pinfunction "2_2") (pintype "passive"))
      (node (ref "R27") (pin "2") (pinfunction "2_2") (pintype "passive"))
    )
    (net (code "17") (name "/INPUT_DIG_6") (class "Default")
      (node (ref "JP12") (pin "2") (pinfunction "2_2") (pintype "passive"))
      (node (ref "R30") (pin "2") (pinfunction "2_2") (pintype "passive"))
    )
    (net (code "18") (name "/IO2-LED") (class "Default")
      (node (ref "SV1") (pin "4") (pinfunction "4_4") (pintype "passive"))
    )
    (net (code "19") (name "/IO4-POWER_PIN") (class "Default")
      (node (ref "SV1") (pin "7") (pinfunction "7_7") (pintype "passive"))
    )
    (net (code "20") (name "/IO12-LED_LILYGO") (class "Default")
      (node (ref "SV1") (pin "5") (pinfunction "5_5") (pintype "passive"))
    )
    (net (code "21") (name "/IO13-DI-RS485") (class "Default")
      (node (ref "JP6") (pin "4") (pinfunction "4_4") (pintype "passive"))
      (node (ref "SV1") (pin "3") (pinfunction "3_3") (pintype "passive"))
    )
    (net (code "22") (name "/IO14-RO-RS485") (class "Default")
      (node (ref "JP6") (pin "1") (pinfunction "1_1") (pintype "passive"))
      (node (ref "SV1") (pin "6") (pinfunction "6_6") (pintype "passive"))
    )
    (net (code "23") (name "/IO23-RE{slash}DE-RS485") (class "Default")
      (node (ref "JP6") (pin "2") (pinfunction "2_2") (pintype "passive"))
      (node (ref "JP6") (pin "3") (pinfunction "3_3") (pintype "passive"))
      (node (ref "SV2") (pin "7") (pinfunction "7_7") (pintype "passive"))
    )
    (net (code "24") (name "/IO25-SIM-PWR") (class "Default")
      (node (ref "SV1") (pin "10") (pinfunction "10_10") (pintype "passive"))
    )
    (net (code "25") (name "/IO26-RX_SIM") (class "Default")
      (node (ref "SV1") (pin "9") (pinfunction "9_9") (pintype "passive"))
    )
    (net (code "26") (name "/IO27-TX_SIM") (class "Default")
      (node (ref "SV1") (pin "8") (pinfunction "8_8") (pintype "passive"))
    )
    (net (code "27") (name "/IO36-S_VP-SIM-IND") (class "Default")
      (node (ref "SV2") (pin "11") (pinfunction "11_11") (pintype "passive"))
    )
    (net (code "28") (name "/N$26") (class "Default")
      (node (ref "Q2") (pin "C") (pinfunction "C_C") (pintype "passive"))
      (node (ref "SW9") (pin "COM") (pinfunction "COM_COM") (pintype "bidirectional"))
    )
    (net (code "29") (name "/N$29") (class "Default")
      (node (ref "Q1") (pin "C") (pinfunction "C_C") (pintype "passive"))
      (node (ref "SW8") (pin "COM") (pinfunction "COM_COM") (pintype "bidirectional"))
    )
    (net (code "30") (name "/N$34") (class "Default")
      (node (ref "Q3") (pin "C") (pinfunction "C_C") (pintype "passive"))
      (node (ref "SW10") (pin "COM") (pinfunction "COM_COM") (pintype "bidirectional"))
    )
    (net (code "31") (name "/RST{slash}EN") (class "Default")
      (node (ref "SV2") (pin "14") (pinfunction "14_14") (pintype "passive"))
    )
    (net (code "32") (name "/SEÑAL_EXT_1") (class "Default")
      (node (ref "JP7") (pin "1") (pinfunction "1_1") (pintype "passive"))
      (node (ref "X1") (pin "1.1") (pinfunction "1A_1.1") (pintype "passive"))
      (node (ref "X1") (pin "1.2") (pinfunction "1A_1.2") (pintype "passive"))
    )
    (net (code "33") (name "/SEÑAL_EXT_2") (class "Default")
      (node (ref "JP8") (pin "1") (pinfunction "1_1") (pintype "passive"))
      (node (ref "X3") (pin "1.1") (pinfunction "1A_1.1") (pintype "passive"))
      (node (ref "X3") (pin "1.2") (pinfunction "1A_1.2") (pintype "passive"))
    )
    (net (code "34") (name "/SEÑAL_EXT_3") (class "Default")
      (node (ref "JP9") (pin "1") (pinfunction "1_1") (pintype "passive"))
      (node (ref "X4") (pin "1.1") (pinfunction "1A_1.1") (pintype "passive"))
      (node (ref "X4") (pin "1.2") (pinfunction "1A_1.2") (pintype "passive"))
    )
    (net (code "35") (name "/SEÑAL_EXT_4") (class "Default")
      (node (ref "JP10") (pin "1") (pinfunction "1_1") (pintype "passive"))
      (node (ref "X5") (pin "1.1") (pinfunction "1A_1.1") (pintype "passive"))
      (node (ref "X5") (pin "1.2") (pinfunction "1A_1.2") (pintype "passive"))
    )
    (net (code "36") (name "/SEÑAL_EXT_5") (class "Default")
      (node (ref "JP11") (pin "1") (pinfunction "1_1") (pintype "passive"))
      (node (ref "X6") (pin "1.1") (pinfunction "1A_1.1") (pintype "passive"))
      (node (ref "X6") (pin "1.2") (pinfunction "1A_1.2") (pintype "passive"))
    )
    (net (code "37") (name "/SEÑAL_EXT_6") (class "Default")
      (node (ref "JP12") (pin "1") (pinfunction "1_1") (pintype "passive"))
      (node (ref "X7") (pin "1.1") (pinfunction "1A_1.1") (pintype "passive"))
      (node (ref "X7") (pin "1.2") (pinfunction "1A_1.2") (pintype "passive"))
    )
    (net (code "38") (name "/U0RXD") (class "Default")
      (node (ref "SV2") (pin "2") (pinfunction "2_2") (pintype "passive"))
    )
    (net (code "39") (name "/U0TXD") (class "Default")
      (node (ref "SV2") (pin "1") (pinfunction "1_1") (pintype "passive"))
    )
    (net (code "40") (name "3.3V") (class "Default")
      (node (ref "C11") (pin "2") (pinfunction "2_2") (pintype "passive"))
      (node (ref "I2C") (pin "1") (pinfunction "S_1") (pintype "passive"))
      (node (ref "JP2") (pin "2") (pinfunction "2_2") (pintype "passive"))
      (node (ref "R13") (pin "1") (pinfunction "1_1") (pintype "passive"))
      (node (ref "R14") (pin "1") (pinfunction "1_1") (pintype "passive"))
      (node (ref "R17") (pin "1") (pinfunction "1_1") (pintype "passive"))
      (node (ref "R20") (pin "1") (pinfunction "1_1") (pintype "passive"))
      (node (ref "R23") (pin "1") (pinfunction "1_1") (pintype "passive"))
      (node (ref "R26") (pin "1") (pinfunction "1_1") (pintype "passive"))
      (node (ref "R29") (pin "1") (pinfunction "1_1") (pintype "passive"))
      (node (ref "R32") (pin "1") (pinfunction "1_1") (pintype "passive"))
      (node (ref "SV1") (pin "15") (pinfunction "15_15") (pintype "passive"))
      (node (ref "SV2") (pin "3") (pinfunction "3_3") (pintype "passive"))
      (node (ref "U$1") (pin "1") (pinfunction "VDD_1") (pintype "power_in"))
    )
    (net (code "41") (name "5V") (class "Default")
      (node (ref "C12") (pin "1") (pinfunction "+_1") (pintype "passive"))
      (node (ref "C13") (pin "+") (pinfunction "+_+") (pintype "passive"))
      (node (ref "C7") (pin "1") (pinfunction "1_1") (pintype "passive"))
      (node (ref "C8") (pin "1") (pinfunction "1_1") (pintype "passive"))
      (node (ref "D1") (pin "C") (pinfunction "C_C") (pintype "passive"))
      (node (ref "D8") (pin "C") (pinfunction "C_C") (pintype "passive"))
      (node (ref "D9") (pin "C") (pinfunction "C_C") (pintype "passive"))
      (node (ref "J3") (pin "P$1") (pinfunction "1_P$1") (pintype "passive"))
      (node (ref "J3") (pin "P$2") (pinfunction "2_P$2") (pintype "passive"))
      (node (ref "JP5") (pin "1") (pinfunction "1_1") (pintype "passive"))
      (node (ref "K1") (pin "1") (pinfunction "1_1") (pintype "passive"))
      (node (ref "K2") (pin "1") (pinfunction "1_1") (pintype "passive"))
      (node (ref "K3") (pin "1") (pinfunction "1_1") (pintype "passive"))
      (node (ref "R39") (pin "1") (pinfunction "1_1") (pintype "passive"))
      (node (ref "SV2") (pin "15") (pinfunction "15_15") (pintype "passive"))
      (node (ref "SW7") (pin "B") (pinfunction "B_B") (pintype "bidirectional"))
      (node (ref "TP15-5V") (pin "1") (pinfunction "1_1") (pintype "passive"))
      (node (ref "U$2") (pin "IN+") (pinfunction "IN+_IN+") (pintype "bidirectional"))
      (node (ref "X8") (pin "1") (pinfunction "1_1") (pintype "passive"))
    )
    (net (code "42") (name "12V") (class "Default")
      (node (ref "C10") (pin "1") (pinfunction "1_1") (pintype "passive"))
      (node (ref "C9") (pin "1") (pinfunction "1_1") (pintype "passive"))
      (node (ref "J7") (pin "P$1") (pinfunction "1_P$1") (pintype "passive"))
      (node (ref "J7") (pin "P$2") (pinfunction "2_P$2") (pintype "passive"))
      (node (ref "R40") (pin "1") (pinfunction "1_1") (pintype "passive"))
      (node (ref "SW7") (pin "A") (pinfunction "A_A") (pintype "bidirectional"))
      (node (ref "TP16-12V") (pin "1") (pinfunction "1_1") (pintype "passive"))
      (node (ref "X12") (pin "1.1") (pinfunction "1A_1.1") (pintype "passive"))
      (node (ref "X12") (pin "1.2") (pinfunction "1A_1.2") (pintype "passive"))
      (node (ref "X14") (pin "1.1") (pinfunction "1A_1.1") (pintype "passive"))
      (node (ref "X14") (pin "1.2") (pinfunction "1A_1.2") (pintype "passive"))
      (node (ref "X14") (pin "5.1") (pinfunction "1A_5.1") (pintype "passive"))
      (node (ref "X14") (pin "5.2") (pinfunction "1A_5.2") (pintype "passive"))
      (node (ref "X14") (pin "9.1") (pinfunction "1A_9.1") (pintype "passive"))
      (node (ref "X14") (pin "9.2") (pinfunction "1A_9.2") (pintype "passive"))
    )
    (net (code "43") (name "GND") (class "Default")
      (node (ref "C1") (pin "2") (pinfunction "2_2") (pintype "passive"))
      (node (ref "C10") (pin "2") (pinfunction "2_2") (pintype "passive"))
      (node (ref "C11") (pin "1") (pinfunction "1_1") (pintype "passive"))
      (node (ref "C12") (pin "2") (pinfunction "-_2") (pintype "passive"))
      (node (ref "C13") (pin "-") (pinfunction "-_-") (pintype "passive"))
      (node (ref "C2") (pin "2") (pinfunction "2_2") (pintype "passive"))
      (node (ref "C3") (pin "2") (pinfunction "2_2") (pintype "passive"))
      (node (ref "C4") (pin "2") (pinfunction "2_2") (pintype "passive"))
      (node (ref "C5") (pin "2") (pinfunction "2_2") (pintype "passive"))
      (node (ref "C6") (pin "2") (pinfunction "2_2") (pintype "passive"))
      (node (ref "C7") (pin "2") (pinfunction "2_2") (pintype "passive"))
      (node (ref "C8") (pin "2") (pinfunction "2_2") (pintype "passive"))
      (node (ref "C9") (pin "2") (pinfunction "2_2") (pintype "passive"))
      (node (ref "CR1") (pin "1") (pinfunction "1_1") (pintype "passive"))
      (node (ref "CR2") (pin "1") (pinfunction "1_1") (pintype "passive"))
      (node (ref "CR3") (pin "1") (pinfunction "1_1") (pintype "passive"))
      (node (ref "CR4") (pin "1") (pinfunction "1_1") (pintype "passive"))
      (node (ref "I2C") (pin "4") (pinfunction "S_4") (pintype "passive"))
      (node (ref "J2") (pin "P$1") (pinfunction "1_P$1") (pintype "passive"))
      (node (ref "J2") (pin "P$2") (pinfunction "2_P$2") (pintype "passive"))
      (node (ref "J4") (pin "P$1") (pinfunction "1_P$1") (pintype "passive"))
      (node (ref "J4") (pin "P$2") (pinfunction "2_P$2") (pintype "passive"))
      (node (ref "J6") (pin "P$1") (pinfunction "1_P$1") (pintype "passive"))
      (node (ref "J6") (pin "P$2") (pinfunction "2_P$2") (pintype "passive"))
      (node (ref "J8") (pin "P$1") (pinfunction "1_P$1") (pintype "passive"))
      (node (ref "J8") (pin "P$2") (pinfunction "2_P$2") (pintype "passive"))
      (node (ref "JP1") (pin "2") (pinfunction "2_2") (pintype "passive"))
      (node (ref "JP5") (pin "4") (pinfunction "4_4") (pintype "passive"))
      (node (ref "LED1") (pin "C") (pinfunction "C_C") (pintype "passive"))
      (node (ref "LED2") (pin "C") (pinfunction "C_C") (pintype "passive"))
      (node (ref "LED3") (pin "C") (pinfunction "C_C") (pintype "passive"))
      (node (ref "OK1") (pin "3") (pinfunction "E_3") (pintype "passive"))
      (node (ref "OK2") (pin "3") (pinfunction "E_3") (pintype "passive"))
      (node (ref "OK3") (pin "3") (pinfunction "E_3") (pintype "passive"))
      (node (ref "OK4") (pin "3") (pinfunction "E_3") (pintype "passive"))
      (node (ref "OK5") (pin "3") (pinfunction "E_3") (pintype "passive"))
      (node (ref "OK6") (pin "3") (pinfunction "E_3") (pintype "passive"))
      (node (ref "Q1") (pin "E") (pinfunction "E_E") (pintype "passive"))
      (node (ref "Q2") (pin "E") (pinfunction "E_E") (pintype "passive"))
      (node (ref "Q3") (pin "E") (pinfunction "E_E") (pintype "passive"))
      (node (ref "R11") (pin "1") (pinfunction "1_1") (pintype "passive"))
      (node (ref "R2") (pin "1") (pinfunction "1_1") (pintype "passive"))
      (node (ref "R34") (pin "1") (pinfunction "1_1") (pintype "passive"))
      (node (ref "R36") (pin "1") (pinfunction "1_1") (pintype "passive"))
      (node (ref "R38") (pin "1") (pinfunction "1_1") (pintype "passive"))
      (node (ref "R5") (pin "1") (pinfunction "1_1") (pintype "passive"))
      (node (ref "R8") (pin "1") (pinfunction "1_1") (pintype "passive"))
      (node (ref "SV1") (pin "1") (pinfunction "1_1") (pintype "passive"))
      (node (ref "SV1") (pin "14") (pinfunction "14_14") (pintype "passive"))
      (node (ref "SV2") (pin "4") (pinfunction "4_4") (pintype "passive"))
      (node (ref "TP1-GND2") (pin "1") (pinfunction "1_1") (pintype "passive"))
      (node (ref "TP1-GND3") (pin "1") (pinfunction "1_1") (pintype "passive"))
      (node (ref "TP2-GND1") (pin "1") (pinfunction "1_1") (pintype "passive"))
      (node (ref "TP2-GND3") (pin "1") (pinfunction "1_1") (pintype "passive"))
      (node (ref "TP2-GND4") (pin "1") (pinfunction "1_1") (pintype "passive"))
      (node (ref "U$1") (pin "2") (pinfunction "GND_2") (pintype "power_in"))
      (node (ref "U$2") (pin "IN-") (pinfunction "IN-_IN-") (pintype "bidirectional"))
      (node (ref "U$2") (pin "OUT-") (pinfunction "OUT-_OUT-") (pintype "bidirectional"))
      (node (ref "X1") (pin "3.1") (pinfunction "1A_3.1") (pintype "passive"))
      (node (ref "X1") (pin "3.2") (pinfunction "1A_3.2") (pintype "passive"))
      (node (ref "X10") (pin "2.1") (pinfunction "1A_2.1") (pintype "passive"))
      (node (ref "X10") (pin "2.2") (pinfunction "1A_2.2") (pintype "passive"))
      (node (ref "X11") (pin "2.1") (pinfunction "1A_2.1") (pintype "passive"))
      (node (ref "X11") (pin "2.2") (pinfunction "1A_2.2") (pintype "passive"))
      (node (ref "X12") (pin "2.1") (pinfunction "1A_2.1") (pintype "passive"))
      (node (ref "X12") (pin "2.2") (pinfunction "1A_2.2") (pintype "passive"))
      (node (ref "X13") (pin "2.1") (pinfunction "1A_2.1") (pintype "passive"))
      (node (ref "X13") (pin "2.2") (pinfunction "1A_2.2") (pintype "passive"))
      (node (ref "X15") (pin "2.1") (pinfunction "1A_2.1") (pintype "passive"))
      (node (ref "X15") (pin "2.2") (pinfunction "1A_2.2") (pintype "passive"))
      (node (ref "X16") (pin "2.1") (pinfunction "1A_2.1") (pintype "passive"))
      (node (ref "X16") (pin "2.2") (pinfunction "1A_2.2") (pintype "passive"))
      (node (ref "X3") (pin "3.1") (pinfunction "1A_3.1") (pintype "passive"))
      (node (ref "X3") (pin "3.2") (pinfunction "1A_3.2") (pintype "passive"))
      (node (ref "X4") (pin "3.1") (pinfunction "1A_3.1") (pintype "passive"))
      (node (ref "X4") (pin "3.2") (pinfunction "1A_3.2") (pintype "passive"))
      (node (ref "X5") (pin "3.1") (pinfunction "1A_3.1") (pintype "passive"))
      (node (ref "X5") (pin "3.2") (pinfunction "1A_3.2") (pintype "passive"))
      (node (ref "X6") (pin "3.1") (pinfunction "1A_3.1") (pintype "passive"))
      (node (ref "X6") (pin "3.2") (pinfunction "1A_3.2") (pintype "passive"))
      (node (ref "X7") (pin "3.1") (pinfunction "1A_3.1") (pintype "passive"))
      (node (ref "X7") (pin "3.2") (pinfunction "1A_3.2") (pintype "passive"))
      (node (ref "X8") (pin "4") (pinfunction "1_4") (pintype "passive"))
      (node (ref "X9") (pin "2.1") (pinfunction "1A_2.1") (pintype "passive"))
      (node (ref "X9") (pin "2.2") (pinfunction "1A_2.2") (pintype "passive"))
    )
    (net (code "44") (name "IO0-DIN-4") (class "Default")
      (node (ref "OK4") (pin "4") (pinfunction "C_4") (pintype "passive"))
      (node (ref "R26") (pin "2") (pinfunction "2_2") (pintype "passive"))
      (node (ref "SV2") (pin "13") (pinfunction "13_13") (pintype "passive"))
      (node (ref "TP8-DIN-4") (pin "1") (pinfunction "1_1") (pintype "passive"))
    )
    (net (code "45") (name "IO5-DOUT-1") (class "Default")
      (node (ref "R33") (pin "1") (pinfunction "1_1") (pintype "passive"))
      (node (ref "SV2") (pin "10") (pinfunction "10_10") (pintype "passive"))
      (node (ref "TP11-DOUT-1") (pin "1") (pinfunction "1_1") (pintype "passive"))
    )
    (net (code "46") (name "IO15-DIN-3") (class "Default")
      (node (ref "OK3") (pin "4") (pinfunction "C_4") (pintype "passive"))
      (node (ref "R23") (pin "2") (pinfunction "2_2") (pintype "passive"))
      (node (ref "SV1") (pin "2") (pinfunction "2_2") (pintype "passive"))
      (node (ref "TP7-DIN-3") (pin "1") (pinfunction "1_1") (pintype "passive"))
    )
    (net (code "47") (name "IO18-DOUT-2") (class "Default")
      (node (ref "R35") (pin "1") (pinfunction "1_1") (pintype "passive"))
      (node (ref "SV2") (pin "9") (pinfunction "9_9") (pintype "passive"))
      (node (ref "TP12-DOUT-2") (pin "1") (pinfunction "1_1") (pintype "passive"))
    )
    (net (code "48") (name "IO19-DOUT-3") (class "Default")
      (node (ref "R37") (pin "1") (pinfunction "1_1") (pintype "passive"))
      (node (ref "SV2") (pin "8") (pinfunction "8_8") (pintype "passive"))
      (node (ref "TP13-DOUT-3") (pin "1") (pinfunction "1_1") (pintype "passive"))
    )
    (net (code "49") (name "IO21-SDA") (class "Default")
      (node (ref "I2C") (pin "2") (pinfunction "S_2") (pintype "passive"))
      (node (ref "JP3") (pin "2") (pinfunction "2_2") (pintype "passive"))
      (node (ref "R13") (pin "2") (pinfunction "2_2") (pintype "passive"))
      (node (ref "SV2") (pin "6") (pinfunction "6_6") (pintype "passive"))
      (node (ref "U$1") (pin "4") (pinfunction "SDA_4") (pintype "bidirectional"))
    )
    (net (code "50") (name "IO22-SCL") (class "Default")
      (node (ref "I2C") (pin "3") (pinfunction "S_3") (pintype "passive"))
      (node (ref "JP4") (pin "2") (pinfunction "2_2") (pintype "passive"))
      (node (ref "R14") (pin "2") (pinfunction "2_2") (pintype "passive"))
      (node (ref "SV2") (pin "5") (pinfunction "5_5") (pintype "passive"))
      (node (ref "U$1") (pin "3") (pinfunction "SCL_3") (pintype "bidirectional"))
    )
    (net (code "51") (name "IO32-DIN-1") (class "Default")
      (node (ref "OK1") (pin "4") (pinfunction "C_4") (pintype "passive"))
      (node (ref "R17") (pin "2") (pinfunction "2_2") (pintype "passive"))
      (node (ref "SV1") (pin "13") (pinfunction "13_13") (pintype "passive"))
      (node (ref "TP5-DIN-1") (pin "1") (pinfunction "1_1") (pintype "passive"))
    )
    (net (code "52") (name "IO33-DIN-2") (class "Default")
      (node (ref "OK2") (pin "4") (pinfunction "C_4") (pintype "passive"))
      (node (ref "R20") (pin "2") (pinfunction "2_2") (pintype "passive"))
      (node (ref "SV1") (pin "12") (pinfunction "12_12") (pintype "passive"))
      (node (ref "TP6-DIN-2") (pin "1") (pinfunction "1_1") (pintype "passive"))
    )
    (net (code "53") (name "IO34-DIN-5") (class "Default")
      (node (ref "OK5") (pin "4") (pinfunction "C_4") (pintype "passive"))
      (node (ref "R29") (pin "2") (pinfunction "2_2") (pintype "passive"))
      (node (ref "SV1") (pin "11") (pinfunction "11_11") (pintype "passive"))
      (node (ref "TP9-DIN-5") (pin "1") (pinfunction "1_1") (pintype "passive"))
    )
    (net (code "54") (name "IO39-S_VN{slash}39-DIN-6") (class "Default")
      (node (ref "OK6") (pin "4") (pinfunction "C_4") (pintype "passive"))
      (node (ref "R32") (pin "2") (pinfunction "2_2") (pintype "passive"))
      (node (ref "SV2") (pin "12") (pinfunction "12_12") (pintype "passive"))
      (node (ref "TP10-DIN-6") (pin "1") (pinfunction "1_1") (pintype "passive"))
    )
    (net (code "55") (name "K1_C1") (class "Default")
      (node (ref "K1") (pin "3") (pinfunction "3_3") (pintype "passive"))
      (node (ref "X14") (pin "3.1") (pinfunction "1A_3.1") (pintype "passive"))
      (node (ref "X14") (pin "3.2") (pinfunction "1A_3.2") (pintype "passive"))
    )
    (net (code "56") (name "K1_C2") (class "Default")
      (node (ref "K1") (pin "2") (pinfunction "2_2") (pintype "passive"))
      (node (ref "X14") (pin "4.1") (pinfunction "1A_4.1") (pintype "passive"))
      (node (ref "X14") (pin "4.2") (pinfunction "1A_4.2") (pintype "passive"))
    )
    (net (code "57") (name "K2_C1") (class "Default")
      (node (ref "K2") (pin "3") (pinfunction "3_3") (pintype "passive"))
      (node (ref "X14") (pin "7.1") (pinfunction "1A_7.1") (pintype "passive"))
      (node (ref "X14") (pin "7.2") (pinfunction "1A_7.2") (pintype "passive"))
    )
    (net (code "58") (name "K2_C2") (class "Default")
      (node (ref "K2") (pin "2") (pinfunction "2_2") (pintype "passive"))
      (node (ref "X14") (pin "8.1") (pinfunction "1A_8.1") (pintype "passive"))
      (node (ref "X14") (pin "8.2") (pinfunction "1A_8.2") (pintype "passive"))
    )
    (net (code "59") (name "K3_C1") (class "Default")
      (node (ref "K3") (pin "3") (pinfunction "3_3") (pintype "passive"))
      (node (ref "X14") (pin "11.1") (pinfunction "1A_11.1") (pintype "passive"))
      (node (ref "X14") (pin "11.2") (pinfunction "1A_11.2") (pintype "passive"))
    )
    (net (code "60") (name "K3_C2") (class "Default")
      (node (ref "K3") (pin "2") (pinfunction "2_2") (pintype "passive"))
      (node (ref "X14") (pin "12.1") (pinfunction "1A_12.1") (pintype "passive"))
      (node (ref "X14") (pin "12.2") (pinfunction "1A_12.2") (pintype "passive"))
    )
    (net (code "61") (name "Net-(CR1-Pad2)") (class "Default")
      (node (ref "CR1") (pin "2") (pinfunction "2_2") (pintype "passive"))
      (node (ref "R1") (pin "2") (pinfunction "2_2") (pintype "passive"))
      (node (ref "R2") (pin "2") (pinfunction "2_2") (pintype "passive"))
      (node (ref "R3") (pin "2") (pinfunction "2_2") (pintype "passive"))
    )
    (net (code "62") (name "Net-(CR2-Pad2)") (class "Default")
      (node (ref "CR2") (pin "2") (pinfunction "2_2") (pintype "passive"))
      (node (ref "R4") (pin "2") (pinfunction "2_2") (pintype "passive"))
      (node (ref "R5") (pin "2") (pinfunction "2_2") (pintype "passive"))
      (node (ref "R6") (pin "2") (pinfunction "2_2") (pintype "passive"))
    )
    (net (code "63") (name "Net-(CR3-Pad2)") (class "Default")
      (node (ref "CR3") (pin "2") (pinfunction "2_2") (pintype "passive"))
      (node (ref "R7") (pin "2") (pinfunction "2_2") (pintype "passive"))
      (node (ref "R8") (pin "2") (pinfunction "2_2") (pintype "passive"))
      (node (ref "R9") (pin "2") (pinfunction "2_2") (pintype "passive"))
    )
    (net (code "64") (name "Net-(CR4-Pad2)") (class "Default")
      (node (ref "CR4") (pin "2") (pinfunction "2_2") (pintype "passive"))
      (node (ref "R10") (pin "2") (pinfunction "2_2") (pintype "passive"))
      (node (ref "R11") (pin "2") (pinfunction "2_2") (pintype "passive"))
      (node (ref "R12") (pin "2") (pinfunction "2_2") (pintype "passive"))
    )
    (net (code "65") (name "Net-(D1-PadA)") (class "Default")
      (node (ref "D1") (pin "A") (pinfunction "A_A") (pintype "passive"))
      (node (ref "K1") (pin "4") (pinfunction "4_4") (pintype "passive"))
      (node (ref "SW8") (pin "A") (pinfunction "A_A") (pintype "bidirectional"))
    )
    (net (code "66") (name "Net-(D2-Pad2)") (class "Default")
      (node (ref "D2") (pin "2") (pinfunction "2_2") (pintype "passive"))
      (node (ref "R15") (pin "1") (pinfunction "1_1") (pintype "passive"))
      (node (ref "R16") (pin "2") (pinfunction "2_2") (pintype "passive"))
    )
    (net (code "67") (name "Net-(D3-Pad2)") (class "Default")
      (node (ref "D3") (pin "2") (pinfunction "2_2") (pintype "passive"))
      (node (ref "R18") (pin "1") (pinfunction "1_1") (pintype "passive"))
      (node (ref "R19") (pin "2") (pinfunction "2_2") (pintype "passive"))
    )
    (net (code "68") (name "Net-(D4-Pad2)") (class "Default")
      (node (ref "D4") (pin "2") (pinfunction "2_2") (pintype "passive"))
      (node (ref "R21") (pin "1") (pinfunction "1_1") (pintype "passive"))
      (node (ref "R22") (pin "2") (pinfunction "2_2") (pintype "passive"))
    )
    (net (code "69") (name "Net-(D5-Pad2)") (class "Default")
      (node (ref "D5") (pin "2") (pinfunction "2_2") (pintype "passive"))
      (node (ref "R24") (pin "1") (pinfunction "1_1") (pintype "passive"))
      (node (ref "R25") (pin "2") (pinfunction "2_2") (pintype "passive"))
    )
    (net (code "70") (name "Net-(D6-Pad2)") (class "Default")
      (node (ref "D6") (pin "2") (pinfunction "2_2") (pintype "passive"))
      (node (ref "R27") (pin "1") (pinfunction "1_1") (pintype "passive"))
      (node (ref "R28") (pin "2") (pinfunction "2_2") (pintype "passive"))
    )
    (net (code "71") (name "Net-(D7-Pad2)") (class "Default")
      (node (ref "D7") (pin "2") (pinfunction "2_2") (pintype "passive"))
      (node (ref "R30") (pin "1") (pinfunction "1_1") (pintype "passive"))
      (node (ref "R31") (pin "2") (pinfunction "2_2") (pintype "passive"))
    )
    (net (code "72") (name "Net-(D8-PadA)") (class "Default")
      (node (ref "D8") (pin "A") (pinfunction "A_A") (pintype "passive"))
      (node (ref "K2") (pin "4") (pinfunction "4_4") (pintype "passive"))
      (node (ref "SW9") (pin "A") (pinfunction "A_A") (pintype "bidirectional"))
    )
    (net (code "73") (name "Net-(D9-PadA)") (class "Default")
      (node (ref "D9") (pin "A") (pinfunction "A_A") (pintype "passive"))
      (node (ref "K3") (pin "4") (pinfunction "4_4") (pintype "passive"))
      (node (ref "SW10") (pin "A") (pinfunction "A_A") (pintype "bidirectional"))
    )
    (net (code "74") (name "Net-(D10-PadA)") (class "Default")
      (node (ref "D10") (pin "A") (pinfunction "A_A") (pintype "passive"))
      (node (ref "SW11") (pin "COM") (pinfunction "COM_COM") (pintype "bidirectional"))
    )
    (net (code "75") (name "Net-(LED1-PadA)") (class "Default")
      (node (ref "LED1") (pin "A") (pinfunction "A_A") (pintype "passive"))
      (node (ref "R39") (pin "2") (pinfunction "2_2") (pintype "passive"))
    )
    (net (code "76") (name "Net-(LED2-PadA)") (class "Default")
      (node (ref "LED2") (pin "A") (pinfunction "A_A") (pintype "passive"))
      (node (ref "R40") (pin "2") (pinfunction "2_2") (pintype "passive"))
    )
    (net (code "77") (name "Net-(LED3-PadA)") (class "Default")
      (node (ref "LED3") (pin "A") (pinfunction "A_A") (pintype "passive"))
      (node (ref "R41") (pin "2") (pinfunction "2_2") (pintype "passive"))
    )
    (net (code "78") (name "Net-(OK1-AC1)") (class "Default")
      (node (ref "OK1") (pin "1") (pinfunction "AC1_1") (pintype "passive"))
      (node (ref "R16") (pin "1") (pinfunction "1_1") (pintype "passive"))
    )
    (net (code "79") (name "Net-(OK1-AC2)") (class "Default")
      (node (ref "D2") (pin "1") (pinfunction "1_1") (pintype "passive"))
      (node (ref "OK1") (pin "2") (pinfunction "AC2_2") (pintype "passive"))
      (node (ref "X1") (pin "2.1") (pinfunction "1A_2.1") (pintype "passive"))
      (node (ref "X1") (pin "2.2") (pinfunction "1A_2.2") (pintype "passive"))
    )
    (net (code "80") (name "Net-(OK2-AC1)") (class "Default")
      (node (ref "OK2") (pin "1") (pinfunction "AC1_1") (pintype "passive"))
      (node (ref "R19") (pin "1") (pinfunction "1_1") (pintype "passive"))
    )
    (net (code "81") (name "Net-(OK2-AC2)") (class "Default")
      (node (ref "D3") (pin "1") (pinfunction "1_1") (pintype "passive"))
      (node (ref "OK2") (pin "2") (pinfunction "AC2_2") (pintype "passive"))
      (node (ref "X3") (pin "2.1") (pinfunction "1A_2.1") (pintype "passive"))
      (node (ref "X3") (pin "2.2") (pinfunction "1A_2.2") (pintype "passive"))
    )
    (net (code "82") (name "Net-(OK3-AC1)") (class "Default")
      (node (ref "OK3") (pin "1") (pinfunction "AC1_1") (pintype "passive"))
      (node (ref "R22") (pin "1") (pinfunction "1_1") (pintype "passive"))
    )
    (net (code "83") (name "Net-(OK3-AC2)") (class "Default")
      (node (ref "D4") (pin "1") (pinfunction "1_1") (pintype "passive"))
      (node (ref "OK3") (pin "2") (pinfunction "AC2_2") (pintype "passive"))
      (node (ref "X4") (pin "2.1") (pinfunction "1A_2.1") (pintype "passive"))
      (node (ref "X4") (pin "2.2") (pinfunction "1A_2.2") (pintype "passive"))
    )
    (net (code "84") (name "Net-(OK4-AC1)") (class "Default")
      (node (ref "OK4") (pin "1") (pinfunction "AC1_1") (pintype "passive"))
      (node (ref "R25") (pin "1") (pinfunction "1_1") (pintype "passive"))
    )
    (net (code "85") (name "Net-(OK4-AC2)") (class "Default")
      (node (ref "D5") (pin "1") (pinfunction "1_1") (pintype "passive"))
      (node (ref "OK4") (pin "2") (pinfunction "AC2_2") (pintype "passive"))
      (node (ref "X5") (pin "2.1") (pinfunction "1A_2.1") (pintype "passive"))
      (node (ref "X5") (pin "2.2") (pinfunction "1A_2.2") (pintype "passive"))
    )
    (net (code "86") (name "Net-(OK5-AC1)") (class "Default")
      (node (ref "OK5") (pin "1") (pinfunction "AC1_1") (pintype "passive"))
      (node (ref "R28") (pin "1") (pinfunction "1_1") (pintype "passive"))
    )
    (net (code "87") (name "Net-(OK5-AC2)") (class "Default")
      (node (ref "D6") (pin "1") (pinfunction "1_1") (pintype "passive"))
      (node (ref "OK5") (pin "2") (pinfunction "AC2_2") (pintype "passive"))
      (node (ref "X6") (pin "2.1") (pinfunction "1A_2.1") (pintype "passive"))
      (node (ref "X6") (pin "2.2") (pinfunction "1A_2.2") (pintype "passive"))
    )
    (net (code "88") (name "Net-(OK6-AC1)") (class "Default")
      (node (ref "OK6") (pin "1") (pinfunction "AC1_1") (pintype "passive"))
      (node (ref "R31") (pin "1") (pinfunction "1_1") (pintype "passive"))
    )
    (net (code "89") (name "Net-(OK6-AC2)") (class "Default")
      (node (ref "D7") (pin "1") (pinfunction "1_1") (pintype "passive"))
      (node (ref "OK6") (pin "2") (pinfunction "AC2_2") (pintype "passive"))
      (node (ref "X7") (pin "2.1") (pinfunction "1A_2.1") (pintype "passive"))
      (node (ref "X7") (pin "2.2") (pinfunction "1A_2.2") (pintype "passive"))
    )
    (net (code "90") (name "Net-(Q1-PadB)") (class "Default")
      (node (ref "Q1") (pin "B") (pinfunction "B_B") (pintype "passive"))
      (node (ref "R33") (pin "2") (pinfunction "2_2") (pintype "passive"))
      (node (ref "R34") (pin "2") (pinfunction "2_2") (pintype "passive"))
    )
    (net (code "91") (name "Net-(Q2-PadB)") (class "Default")
      (node (ref "Q2") (pin "B") (pinfunction "B_B") (pintype "passive"))
      (node (ref "R35") (pin "2") (pinfunction "2_2") (pintype "passive"))
      (node (ref "R36") (pin "2") (pinfunction "2_2") (pintype "passive"))
    )
    (net (code "92") (name "Net-(Q3-PadB)") (class "Default")
      (node (ref "Q3") (pin "B") (pinfunction "B_B") (pintype "passive"))
      (node (ref "R37") (pin "2") (pinfunction "2_2") (pintype "passive"))
      (node (ref "R38") (pin "2") (pinfunction "2_2") (pintype "passive"))
    )
    (net (code "93") (name "Net-(R7-Pad1)") (class "Default")
      (node (ref "R7") (pin "1") (pinfunction "1_1") (pintype "passive"))
      (node (ref "X15") (pin "1.1") (pinfunction "1A_1.1") (pintype "passive"))
      (node (ref "X15") (pin "1.2") (pinfunction "1A_1.2") (pintype "passive"))
    )
    (net (code "94") (name "Net-(R10-Pad1)") (class "Default")
      (node (ref "R10") (pin "1") (pinfunction "1_1") (pintype "passive"))
      (node (ref "X16") (pin "1.1") (pinfunction "1A_1.1") (pintype "passive"))
      (node (ref "X16") (pin "1.2") (pinfunction "1A_1.2") (pintype "passive"))
    )
    (net (code "95") (name "Net-(SW11-PadA)") (class "Default")
      (node (ref "SW11") (pin "A") (pinfunction "A_A") (pintype "bidirectional"))
      (node (ref "X11") (pin "1.1") (pinfunction "1A_1.1") (pintype "passive"))
      (node (ref "X11") (pin "1.2") (pinfunction "1A_1.2") (pintype "passive"))
    )
    (net (code "96") (name "Net-(U$1-ADDR)") (class "Default")
      (node (ref "JP1") (pin "1") (pinfunction "1_1") (pintype "passive"))
      (node (ref "JP2") (pin "1") (pinfunction "1_1") (pintype "passive"))
      (node (ref "JP3") (pin "1") (pinfunction "1_1") (pintype "passive"))
      (node (ref "JP4") (pin "1") (pinfunction "1_1") (pintype "passive"))
      (node (ref "U$1") (pin "5") (pinfunction "ADDR_5") (pintype "bidirectional"))
    )
    (net (code "97") (name "OPEN_COLECTOR_1") (class "Default")
      (node (ref "SW8") (pin "B") (pinfunction "B_B") (pintype "bidirectional"))
      (node (ref "X14") (pin "2.1") (pinfunction "1A_2.1") (pintype "passive"))
      (node (ref "X14") (pin "2.2") (pinfunction "1A_2.2") (pintype "passive"))
    )
    (net (code "98") (name "OPEN_COLECTOR_2") (class "Default")
      (node (ref "SW9") (pin "B") (pinfunction "B_B") (pintype "bidirectional"))
      (node (ref "X14") (pin "6.1") (pinfunction "1A_6.1") (pintype "passive"))
      (node (ref "X14") (pin "6.2") (pinfunction "1A_6.2") (pintype "passive"))
    )
    (net (code "99") (name "OPEN_COLECTOR_3") (class "Default")
      (node (ref "SW10") (pin "B") (pinfunction "B_B") (pintype "bidirectional"))
      (node (ref "X14") (pin "10.1") (pinfunction "1A_10.1") (pintype "passive"))
      (node (ref "X14") (pin "10.2") (pinfunction "1A_10.2") (pintype "passive"))
    )
    (net (code "100") (name "unconnected-(SW11-PadB)") (class "Default")
      (node (ref "SW11") (pin "B") (pinfunction "B_B") (pintype "bidirectional"))
    )
    (net (code "101") (name "unconnected-(U$1-ALRT-Pad6)") (class "Default")
      (node (ref "U$1") (pin "6") (pinfunction "ALRT_6") (pintype "bidirectional"))
    )
  )
)
